# SCH_LM2596_Board_V1_2023-05-05.net
KiCad netlist of a schematic drawn in EasyEDA
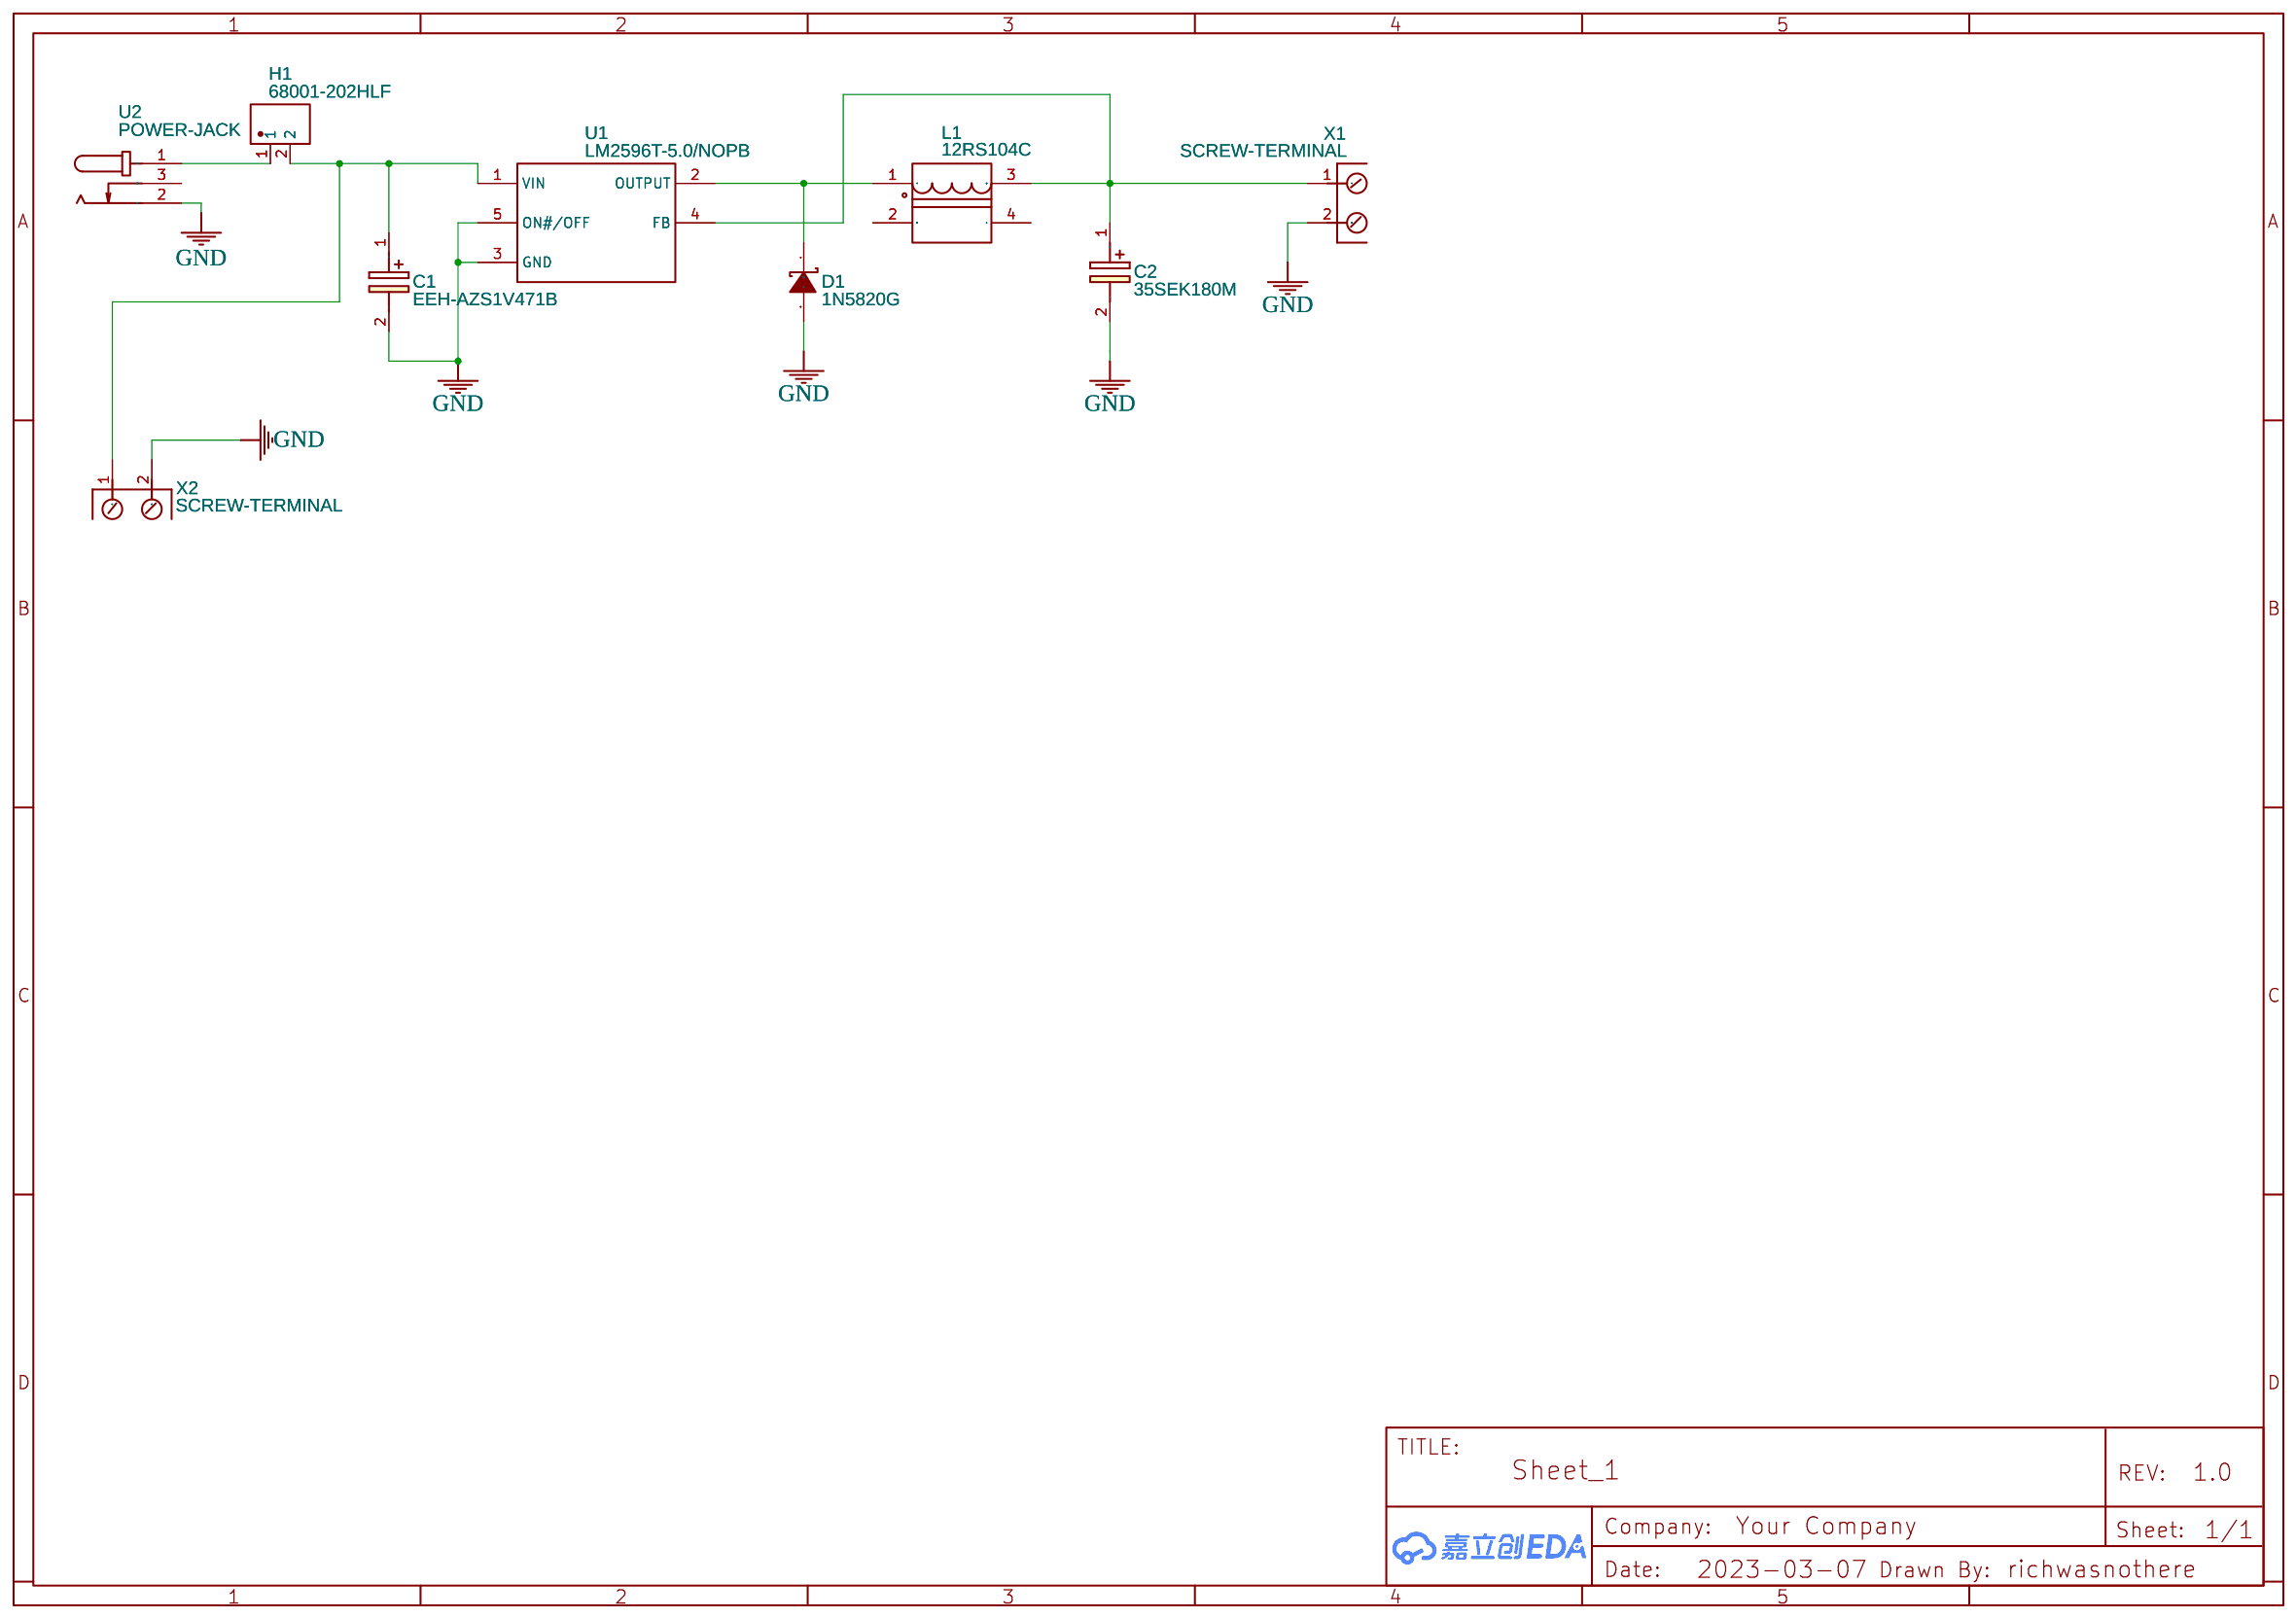
[diagram p0: schematic sheet]

(export (version "E")
  (design (tool "Eeschema 10.0.6"))
  (components
    (comp (ref "C1") (value "EEH-AZS1V471B") (libsource (lib "") (part "EEH-AZS1V471B")))
    (comp (ref "C2") (value "35SEK180M") (libsource (lib "") (part "35SEK180M")))
    (comp (ref "D1")
      (value "1N5820G")
      (fields (field (name "BOM_Supplier Part") "C95400"))
      (libsource (lib "") (part "1N5820G"))
    )
    (comp (ref "H1")
      (value "68001-202HLF")
      (fields (field (name "BOM_Supplier Part") "C2931354"))
      (libsource (lib "") (part "68001-202HLF"))
    )
    (comp (ref "L1")
      (value "12RS104C")
      (fields (field (name "BOM_Supplier Part") "C3039630"))
      (libsource (lib "") (part "12RS104C"))
    )
    (comp (ref "U1")
      (value "LM2596T-5.0/NOPB")
      (fields (field (name "BOM_Supplier Part") "C9714"))
      (libsource (lib "") (part "LM2596T-5.0/NOPB"))
    )
    (comp (ref "U2")
      (value "POWER-JACK")
      (fields (field (name "BOM_Supplier Part") "C9900001795"))
      (libsource (lib "") (part "POWER-JACK"))
    )
    (comp (ref "X1")
      (value "SCREW-TERMINAL")
      (fields (field (name "BOM_Manufacturer Part") "?"))
      (libsource (lib "") (part "Unknown_675_-720"))
    )
    (comp (ref "X2")
      (value "SCREW-TERMINAL")
      (fields (field (name "BOM_Manufacturer Part") "?"))
      (libsource (lib "") (part "Unknown_50_-560"))
    )
  )
  (nets
    (net (code "1") (name "GND") (class "Default")
      (node (ref "C1") (pin "2") (pinfunction "-_2") (pintype "bidirectional"))
      (node (ref "C2") (pin "2") (pinfunction "-_2") (pintype "bidirectional"))
      (node (ref "D1") (pin "2") (pinfunction "A_2") (pintype "unspecified"))
      (node (ref "U1") (pin "3") (pinfunction "GND_3") (pintype "passive"))
      (node (ref "U1") (pin "5") (pinfunction "ON#/OFF_5") (pintype "unspecified"))
      (node (ref "U2") (pin "2") (pinfunction "2_2") (pintype "unspecified"))
      (node (ref "X1") (pin "2") (pinfunction "2_2") (pintype "unspecified"))
      (node (ref "X2") (pin "2") (pinfunction "2_2") (pintype "unspecified"))
    )
    (net (code "2") (name "Net-(C1-+)") (class "Default")
      (node (ref "C1") (pin "1") (pinfunction "+_1") (pintype "bidirectional"))
      (node (ref "H1") (pin "2") (pinfunction "2_2") (pintype "unspecified"))
      (node (ref "U1") (pin "1") (pinfunction "VIN_1") (pintype "passive"))
      (node (ref "X2") (pin "1") (pinfunction "1_1") (pintype "unspecified"))
    )
    (net (code "3") (name "Net-(C2-+)") (class "Default")
      (node (ref "C2") (pin "1") (pinfunction "+_1") (pintype "bidirectional"))
      (node (ref "L1") (pin "3") (pinfunction "3_3") (pintype "unspecified"))
      (node (ref "U1") (pin "4") (pinfunction "FB_4") (pintype "unspecified"))
      (node (ref "X1") (pin "1") (pinfunction "1_1") (pintype "unspecified"))
    )
    (net (code "4") (name "Net-(D1-C)") (class "Default")
      (node (ref "D1") (pin "1") (pinfunction "C_1") (pintype "unspecified"))
      (node (ref "L1") (pin "1") (pinfunction "1_1") (pintype "unspecified"))
      (node (ref "U1") (pin "2") (pinfunction "OUTPUT_2") (pintype "passive"))
    )
    (net (code "5") (name "Net-(H1-Pad1)") (class "Default")
      (node (ref "H1") (pin "1") (pinfunction "1_1") (pintype "unspecified"))
      (node (ref "U2") (pin "1") (pinfunction "1_1") (pintype "unspecified"))
    )
    (net (code "6") (name "unconnected-(L1-Pad2)") (class "Default")
      (node (ref "L1") (pin "2") (pinfunction "2_2") (pintype "unspecified"))
    )
    (net (code "7") (name "unconnected-(L1-Pad4)") (class "Default")
      (node (ref "L1") (pin "4") (pinfunction "4_4") (pintype "unspecified"))
    )
    (net (code "8") (name "unconnected-(U2-Pad3)") (class "Default")
      (node (ref "U2") (pin "3") (pinfunction "3_3") (pintype "unspecified"))
    )
  )
)
